# MCU.net
KiCad netlist of a schematic drawn in Altium Designer
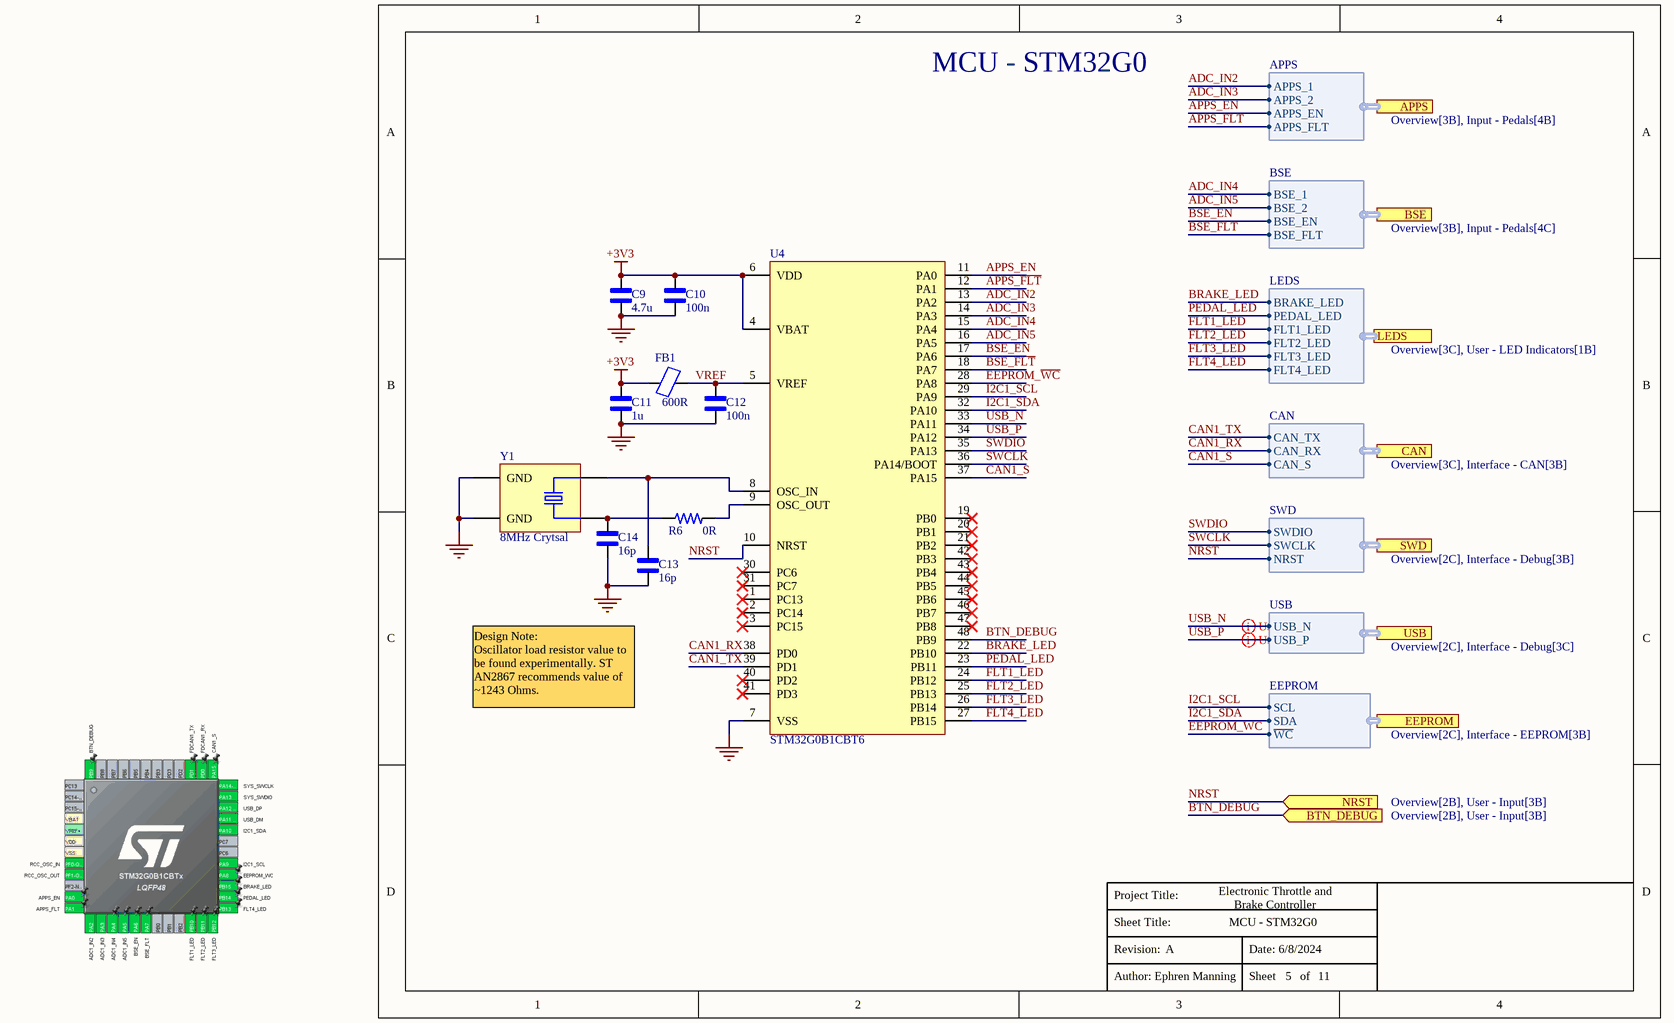
[diagram p0: MCU.SchDoc]

(export (version "E")
  (design (tool "Eeschema 10.0.6"))
  (components
    (comp (ref "C9")
      (value "4.7u")
      (footprint "CAP_0402-Footprint-1")
      (description "4.7uF 10V 20% 0402 CAP")
      (fields (field (name "DIGIKEY PART NUMBER") "1276-1482-1-ND"))
      (libsource (lib "SAE @ UIC Formula Electric") (part "CAP_0402-Symbol-1"))
    )
    (comp (ref "C10")
      (value "100n")
      (footprint "CAP_0402-Footprint-1")
      (description "100nF 10V 10% 0402 CAP")
      (fields (field (name "DIGIKEY PART NUMBER") "1276-1002-1-ND"))
      (libsource (lib "SAE @ UIC Formula Electric") (part "CAP_0402-Symbol-1"))
    )
    (comp (ref "C11")
      (value "1u")
      (footprint "CAP_0402-Footprint-1")
      (description "1uF 10V 10% 0402 CAP")
      (fields (field (name "DIGIKEY PART NUMBER") "1276-1076-1-ND"))
      (libsource (lib "SAE @ UIC Formula Electric") (part "CAP_0402-Symbol-1"))
    )
    (comp (ref "C12")
      (value "100n")
      (footprint "CAP_0402-Footprint-1")
      (description "100nF 10V 10% 0402 CAP")
      (fields (field (name "DIGIKEY PART NUMBER") "1276-1002-1-ND"))
      (libsource (lib "SAE @ UIC Formula Electric") (part "CAP_0402-Symbol-1"))
    )
    (comp (ref "C13")
      (value "16p")
      (footprint "CAP_0402-Footprint-1")
      (description "16pF 50V 1% 0402 Ceramic Capacitor")
      (fields (field (name "DIGIKEY PART NUMBER") "490-GJM1555C1H160FB01JCT-ND"))
      (libsource (lib "") (part "CAP_0402-Symbol-1_1"))
    )
    (comp (ref "C14")
      (value "16p")
      (footprint "CAP_0402-Footprint-1")
      (description "16pF 50V 1% 0402 Ceramic Capacitor")
      (fields (field (name "DIGIKEY PART NUMBER") "490-GJM1555C1H160FB01JCT-ND"))
      (libsource (lib "SAE @ UIC Formula Electric") (part "CAP_0402-Symbol-1"))
    )
    (comp (ref "FB1")
      (value "600R")
      (footprint "FB_0402-Footprint-1")
      (description "600R@100MHz 300mA 0402 Ferrite Bead")
      (fields (field (name "DIGIKEY PART NUMBER") "490-1006-1-ND"))
      (libsource (lib "SAE @ UIC Formula Electric") (part "FB_0402-Symbol"))
    )
    (comp (ref "R6")
      (value "0R")
      (footprint "RES_0402-Footprint-1")
      (description "0 Ohm 1/16W 0402 Resistor")
      (fields (field (name "DIGIKEY PART NUMBER") "311-0.0JRCT-ND"))
      (libsource (lib "SAE @ UIC Formula Electric") (part "RES_0402_Symbol"))
    )
    (comp (ref "U4")
      (value "STM32G0B1CBT6")
      (footprint "STM32G0-LQFP48")
      (description "32-bit Cortex-M0+ MCU 48LQFP")
      (fields (field (name "DIGIKEY PART NUMBER") "497-STM32G0B1CBT6-ND"))
      (libsource (lib "SAE @ UIC Formula Electric") (part "STM32G0B1CBT6-Symbol-1"))
    )
    (comp (ref "Y1")
      (value "ECS-80-18-33-JGN-TR")
      (footprint "XTAL_ECS-240-8-33-AGN-TR")
      (description "8MHz ±20ppm 18pF Crystal")
      (fields (field (name "DIGIKEY PART NUMBER") "50-ECS-80-18-33-JGN-CT-ND"))
      (libsource (lib "SAE @ UIC Formula Electric") (part "ECS-80-18-33-JGN-TR"))
    )
  )
  (nets
    (net (code "8") (name "+3V3") (class "Default")
      (node (ref "C10") (pin "2") (pinfunction "2_2") (pintype "passive"))
      (node (ref "C11") (pin "2") (pinfunction "2_2") (pintype "passive"))
      (node (ref "C9") (pin "2") (pinfunction "2_2") (pintype "passive"))
      (node (ref "FB1") (pin "1") (pinfunction "1_1") (pintype "passive"))
      (node (ref "U4") (pin "4") (pinfunction "VBAT_4") (pintype "passive"))
      (node (ref "U4") (pin "6") (pinfunction "VDD_6") (pintype "passive"))
    )
    (net (code "9") (name "/ADC_IN2") (class "Default")
      (node (ref "U4") (pin "13") (pinfunction "PA2_13") (pintype "passive"))
    )
    (net (code "10") (name "/ADC_IN3") (class "Default")
      (node (ref "U4") (pin "14") (pinfunction "PA3_14") (pintype "passive"))
    )
    (net (code "11") (name "/ADC_IN4") (class "Default")
      (node (ref "U4") (pin "15") (pinfunction "PA4_15") (pintype "passive"))
    )
    (net (code "12") (name "/ADC_IN5") (class "Default")
      (node (ref "U4") (pin "16") (pinfunction "PA5_16") (pintype "passive"))
    )
    (net (code "13") (name "/APPS_EN") (class "Default")
      (node (ref "U4") (pin "11") (pinfunction "PA0_11") (pintype "passive"))
    )
    (net (code "14") (name "/APPS_~{FLT}") (class "Default")
      (node (ref "U4") (pin "12") (pinfunction "PA1_12") (pintype "passive"))
    )
    (net (code "15") (name "/BRAKE_LED") (class "Default")
      (node (ref "U4") (pin "22") (pinfunction "PB10_22") (pintype "passive"))
    )
    (net (code "16") (name "/BSE_EN") (class "Default")
      (node (ref "U4") (pin "17") (pinfunction "PA6_17") (pintype "passive"))
    )
    (net (code "17") (name "/BSE_~{FLT}") (class "Default")
      (node (ref "U4") (pin "18") (pinfunction "PA7_18") (pintype "passive"))
    )
    (net (code "18") (name "/BTN_DEBUG") (class "Default")
      (node (ref "U4") (pin "48") (pinfunction "PB9_48") (pintype "passive"))
    )
    (net (code "19") (name "/CAN1_RX") (class "Default")
      (node (ref "U4") (pin "38") (pinfunction "PD0_38") (pintype "passive"))
    )
    (net (code "20") (name "/CAN1_S") (class "Default")
      (node (ref "U4") (pin "37") (pinfunction "PA15_37") (pintype "passive"))
    )
    (net (code "21") (name "/CAN1_TX") (class "Default")
      (node (ref "U4") (pin "39") (pinfunction "PD1_39") (pintype "passive"))
    )
    (net (code "22") (name "/EEPROM_~{WC}") (class "Default")
      (node (ref "U4") (pin "28") (pinfunction "PA8_28") (pintype "passive"))
    )
    (net (code "23") (name "/FLT1_LED") (class "Default")
      (node (ref "U4") (pin "24") (pinfunction "PB12_24") (pintype "passive"))
    )
    (net (code "24") (name "/FLT2_LED") (class "Default")
      (node (ref "U4") (pin "25") (pinfunction "PB13_25") (pintype "passive"))
    )
    (net (code "25") (name "/FLT3_LED") (class "Default")
      (node (ref "U4") (pin "26") (pinfunction "PB14_26") (pintype "passive"))
    )
    (net (code "26") (name "/FLT4_LED") (class "Default")
      (node (ref "U4") (pin "27") (pinfunction "PB15_27") (pintype "passive"))
    )
    (net (code "27") (name "/I2C1_SCL") (class "Default")
      (node (ref "U4") (pin "29") (pinfunction "PA9_29") (pintype "passive"))
    )
    (net (code "28") (name "/I2C1_SDA") (class "Default")
      (node (ref "U4") (pin "32") (pinfunction "PA10_32") (pintype "passive"))
    )
    (net (code "29") (name "/NRST") (class "Default")
      (node (ref "U4") (pin "10") (pinfunction "NRST_10") (pintype "passive"))
    )
    (net (code "30") (name "/PEDAL_LED") (class "Default")
      (node (ref "U4") (pin "23") (pinfunction "PB11_23") (pintype "passive"))
    )
    (net (code "31") (name "/SWCLK") (class "Default")
      (node (ref "U4") (pin "36") (pinfunction "PA14/BOOT_36") (pintype "passive"))
    )
    (net (code "32") (name "/SWDIO") (class "Default")
      (node (ref "U4") (pin "35") (pinfunction "PA13_35") (pintype "passive"))
    )
    (net (code "33") (name "/USB_N") (class "Default")
      (node (ref "U4") (pin "33") (pinfunction "PA11_33") (pintype "passive"))
    )
    (net (code "34") (name "/USB_P") (class "Default")
      (node (ref "U4") (pin "34") (pinfunction "PA12_34") (pintype "passive"))
    )
    (net (code "35") (name "/VREF") (class "Default")
      (node (ref "C12") (pin "2") (pinfunction "2_2") (pintype "passive"))
      (node (ref "FB1") (pin "2") (pinfunction "2_2") (pintype "passive"))
      (node (ref "U4") (pin "5") (pinfunction "VREF_5") (pintype "passive"))
    )
    (net (code "43") (name "GND") (class "Default")
      (node (ref "C10") (pin "1") (pinfunction "1_1") (pintype "passive"))
      (node (ref "C11") (pin "1") (pinfunction "1_1") (pintype "passive"))
      (node (ref "C12") (pin "1") (pinfunction "1_1") (pintype "passive"))
      (node (ref "C13") (pin "2") (pinfunction "2_2") (pintype "passive"))
      (node (ref "C14") (pin "1") (pinfunction "1_1") (pintype "passive"))
      (node (ref "C9") (pin "1") (pinfunction "1_1") (pintype "passive"))
      (node (ref "U4") (pin "7") (pinfunction "VSS_7") (pintype "passive"))
      (node (ref "Y1") (pin "2") (pinfunction "GND_2") (pintype "power_in"))
      (node (ref "Y1") (pin "4") (pinfunction "GND_4") (pintype "power_in"))
    )
    (net (code "44") (name "Net-(U4-OSC_IN)") (class "Default")
      (node (ref "C13") (pin "1") (pinfunction "1_1") (pintype "passive"))
      (node (ref "U4") (pin "8") (pinfunction "OSC_IN_8") (pintype "passive"))
      (node (ref "Y1") (pin "1") (pinfunction "IN/OUT_1") (pintype "passive"))
    )
    (net (code "45") (name "Net-(U4-OSC_OUT)") (class "Default")
      (node (ref "R6") (pin "2") (pinfunction "2_2") (pintype "passive"))
      (node (ref "U4") (pin "9") (pinfunction "OSC_OUT_9") (pintype "passive"))
    )
    (net (code "46") (name "Net-(Y1-OUT{slash}IN)") (class "Default")
      (node (ref "C14") (pin "2") (pinfunction "2_2") (pintype "passive"))
      (node (ref "R6") (pin "1") (pinfunction "1_1") (pintype "passive"))
      (node (ref "Y1") (pin "3") (pinfunction "OUT/IN_3") (pintype "passive"))
    )
    (net (code "47") (name "unconnected-(U4-PB0-Pad19)") (class "Default")
      (node (ref "U4") (pin "19") (pinfunction "PB0_19") (pintype "passive+no_connect"))
    )
    (net (code "48") (name "unconnected-(U4-PB1-Pad20)") (class "Default")
      (node (ref "U4") (pin "20") (pinfunction "PB1_20") (pintype "passive+no_connect"))
    )
    (net (code "49") (name "unconnected-(U4-PB2-Pad21)") (class "Default")
      (node (ref "U4") (pin "21") (pinfunction "PB2_21") (pintype "passive+no_connect"))
    )
    (net (code "50") (name "unconnected-(U4-PB3-Pad42)") (class "Default")
      (node (ref "U4") (pin "42") (pinfunction "PB3_42") (pintype "passive+no_connect"))
    )
    (net (code "51") (name "unconnected-(U4-PB4-Pad43)") (class "Default")
      (node (ref "U4") (pin "43") (pinfunction "PB4_43") (pintype "passive+no_connect"))
    )
    (net (code "52") (name "unconnected-(U4-PB5-Pad44)") (class "Default")
      (node (ref "U4") (pin "44") (pinfunction "PB5_44") (pintype "passive+no_connect"))
    )
    (net (code "53") (name "unconnected-(U4-PB6-Pad45)") (class "Default")
      (node (ref "U4") (pin "45") (pinfunction "PB6_45") (pintype "passive+no_connect"))
    )
    (net (code "54") (name "unconnected-(U4-PB7-Pad46)") (class "Default")
      (node (ref "U4") (pin "46") (pinfunction "PB7_46") (pintype "passive+no_connect"))
    )
    (net (code "55") (name "unconnected-(U4-PB8-Pad47)") (class "Default")
      (node (ref "U4") (pin "47") (pinfunction "PB8_47") (pintype "passive+no_connect"))
    )
    (net (code "56") (name "unconnected-(U4-PC6-Pad30)") (class "Default")
      (node (ref "U4") (pin "30") (pinfunction "PC6_30") (pintype "passive+no_connect"))
    )
    (net (code "57") (name "unconnected-(U4-PC7-Pad31)") (class "Default")
      (node (ref "U4") (pin "31") (pinfunction "PC7_31") (pintype "passive+no_connect"))
    )
    (net (code "58") (name "unconnected-(U4-PC13-Pad1)") (class "Default")
      (node (ref "U4") (pin "1") (pinfunction "PC13_1") (pintype "passive+no_connect"))
    )
    (net (code "59") (name "unconnected-(U4-PC14-Pad2)") (class "Default")
      (node (ref "U4") (pin "2") (pinfunction "PC14_2") (pintype "passive+no_connect"))
    )
    (net (code "60") (name "unconnected-(U4-PC15-Pad3)") (class "Default")
      (node (ref "U4") (pin "3") (pinfunction "PC15_3") (pintype "passive+no_connect"))
    )
    (net (code "61") (name "unconnected-(U4-PD2-Pad40)") (class "Default")
      (node (ref "U4") (pin "40") (pinfunction "PD2_40") (pintype "passive+no_connect"))
    )
    (net (code "62") (name "unconnected-(U4-PD3-Pad41)") (class "Default")
      (node (ref "U4") (pin "41") (pinfunction "PD3_41") (pintype "passive+no_connect"))
    )
  )
)
